# Rus.net
KiCad netlist of a schematic drawn in Altium Designer
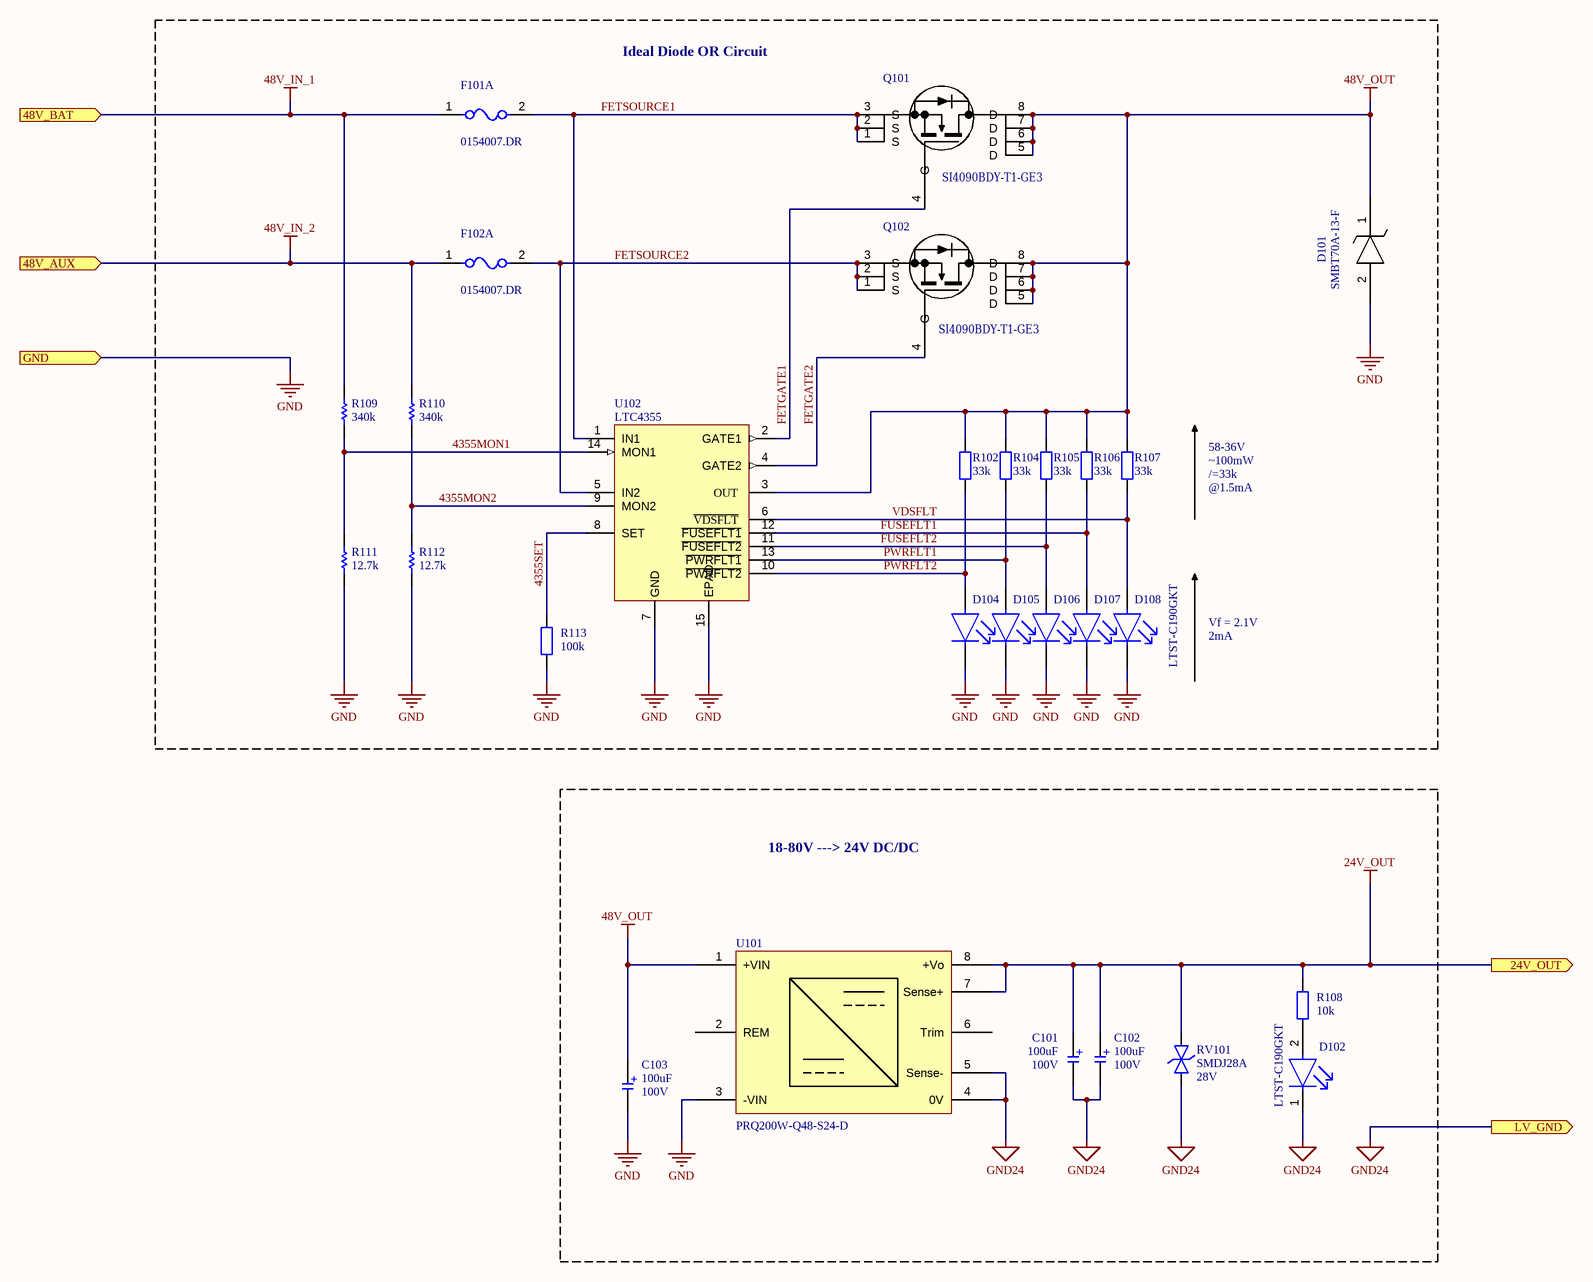
[diagram p0: Rus.SchDoc]

(export (version "E")
  (design (tool "Eeschema 10.0.6"))
  (components
    (comp (ref "C101")
      (value "EMVE101ARA101MKE0S")
      (footprint "CAP ALSMD ELEC 12.5MM H13MM")
      (description "Generic Polarised Capacitor")
      (fields
        (field (name "TOLERANCE") "20%")
        (field (name "VOLTAGE RATING") "100V")
        (field (name "CAPACITANCE") "100uF")
        (field (name "MANUFACTURER") "United Chemi-Con")
      )
      (libsource (lib "DMR_common_lib") (part "C_POL"))
    )
    (comp (ref "C102")
      (value "EMVE101ARA101MKE0S")
      (footprint "CAP ALSMD ELEC 12.5MM H13MM")
      (description "Generic Polarised Capacitor")
      (fields
        (field (name "TOLERANCE") "20%")
        (field (name "VOLTAGE RATING") "100V")
        (field (name "CAPACITANCE") "100uF")
        (field (name "MANUFACTURER") "United Chemi-Con")
      )
      (libsource (lib "DMR_common_lib") (part "C_POL"))
    )
    (comp (ref "C103")
      (value "EMVE101ARA101MKE0S")
      (footprint "CAP ALSMD ELEC 12.5MM H13MM")
      (description "Generic Polarised Capacitor")
      (fields
        (field (name "TOLERANCE") "20%")
        (field (name "VOLTAGE RATING") "100V")
        (field (name "CAPACITANCE") "100uF")
        (field (name "MANUFACTURER") "United Chemi-Con")
      )
      (libsource (lib "DMR_common_lib") (part "C_POL"))
    )
    (comp (ref "D101")
      (value "SMBT70A-13-F")
      (footprint "SMBT70A-13-F")
      (description "SMBJ Series 70 V 600 W Surface Mount Uni-Directional TVS Diode - DO-214AA")
      (fields (field (name "MANUFACTURER") "Diodes"))
      (libsource (lib "Schlib1") (part "SMBT70A-13-F"))
    )
    (comp (ref "D102")
      (value "LTST-C190GKT")
      (footprint "FP-LTST-C190GKT-MFG")
      (description "LED GREEN CLEAR CHIP SMD")
      (fields (field (name "VOLTAGE") "2V"))
      (libsource (lib "") (part "8706943c75ba83719d021d2fdc84c58_1"))
    )
    (comp (ref "D104")
      (value "LTST-C190GKT")
      (footprint "FP-LTST-C190GKT-MFG")
      (description "LED GREEN CLEAR CHIP SMD")
      (fields (field (name "VOLTAGE") "2V"))
      (libsource (lib "Altium Content Vault") (part "8706943c75ba83719d021d2fdc84c58"))
    )
    (comp (ref "D105")
      (value "LTST-C190GKT")
      (footprint "FP-LTST-C190GKT-MFG")
      (description "LED GREEN CLEAR CHIP SMD")
      (fields (field (name "VOLTAGE") "2V"))
      (libsource (lib "Altium Content Vault") (part "8706943c75ba83719d021d2fdc84c58"))
    )
    (comp (ref "D106")
      (value "LTST-C190GKT")
      (footprint "FP-LTST-C190GKT-MFG")
      (description "LED GREEN CLEAR CHIP SMD")
      (fields (field (name "VOLTAGE") "2V"))
      (libsource (lib "Altium Content Vault") (part "8706943c75ba83719d021d2fdc84c58"))
    )
    (comp (ref "D107")
      (value "LTST-C190GKT")
      (footprint "FP-LTST-C190GKT-MFG")
      (description "LED GREEN CLEAR CHIP SMD")
      (fields (field (name "VOLTAGE") "2V"))
      (libsource (lib "Altium Content Vault") (part "8706943c75ba83719d021d2fdc84c58"))
    )
    (comp (ref "D108")
      (value "LTST-C190GKT")
      (footprint "FP-LTST-C190GKT-MFG")
      (description "LED GREEN CLEAR CHIP SMD")
      (fields (field (name "VOLTAGE") "2V"))
      (libsource (lib "Altium Content Vault") (part "8706943c75ba83719d021d2fdc84c58"))
    )
    (comp (ref "F101A")
      (value "0154007.DR")
      (footprint "FP-0154-MFG")
      (description "FUSE BRD MNT 7A 125VAC/VDC 2SMD")
      (fields
        (field (name "OCTOPART") "https://octopart.com/0154007.dr-littelfuse-565863")
        (field (name "MANUFACTURER") "Littelfuse Inc")
      )
      (libsource (lib "Altium Content Vault") (part "5bcf9b9f640e542cf0359d10258e979"))
    )
    (comp (ref "F102A")
      (value "0154007.DR")
      (footprint "FP-0154-MFG")
      (description "FUSE BRD MNT 7A 125VAC/VDC 2SMD")
      (fields
        (field (name "OCTOPART") "https://octopart.com/0154007.dr-littelfuse-565863")
        (field (name "MANUFACTURER") "Littelfuse Inc")
      )
      (libsource (lib "Altium Content Vault") (part "5bcf9b9f640e542cf0359d10258e979"))
    )
    (comp (ref "Q101")
      (value "‎SI4090BDY-T1-GE3‎")
      (footprint "SOIC127P600X175-8N")
      (fields (field (name "MANUFACTURER PART NUMBER") "SI4090BDY-T1-GE3"))
      (libsource (lib "Schlib1") (part "‎SI4090BDY-T1-GE3‎"))
    )
    (comp (ref "Q102")
      (value "‎SI4090BDY-T1-GE3‎")
      (footprint "SOIC127P600X175-8N")
      (fields (field (name "MANUFACTURER PART NUMBER") "SI4090BDY-T1-GE3"))
      (libsource (lib "Schlib1") (part "‎SI4090BDY-T1-GE3‎"))
    )
    (comp (ref "R102")
      (value "33k")
      (footprint "RES 0603_1608 RF")
      (description "Generic Resistor")
      (fields (field (name "TOLERANCE") "1%"))
      (libsource (lib "DMR_common_lib") (part "R"))
    )
    (comp (ref "R104")
      (value "33k")
      (footprint "RES 0603_1608 RF")
      (description "Generic Resistor")
      (fields (field (name "TOLERANCE") "1%"))
      (libsource (lib "DMR_common_lib") (part "R"))
    )
    (comp (ref "R105")
      (value "33k")
      (footprint "RES 0603_1608 RF")
      (description "Generic Resistor")
      (fields (field (name "TOLERANCE") "1%"))
      (libsource (lib "DMR_common_lib") (part "R"))
    )
    (comp (ref "R106")
      (value "33k")
      (footprint "RES 0603_1608 RF")
      (description "Generic Resistor")
      (fields (field (name "TOLERANCE") "1%"))
      (libsource (lib "DMR_common_lib") (part "R"))
    )
    (comp (ref "R107")
      (value "33k")
      (footprint "RES 0603_1608 RF")
      (description "Generic Resistor")
      (fields (field (name "TOLERANCE") "1%"))
      (libsource (lib "DMR_common_lib") (part "R"))
    )
    (comp (ref "R108")
      (value "10k")
      (footprint "RES 0402_1005 RF")
      (description "Generic Resistor")
      (fields (field (name "TOLERANCE") "1%"))
      (libsource (lib "DMR_common_lib") (part "R"))
    )
    (comp (ref "R109")
      (value "ERA6AEB3403V")
      (footprint "RESC2013X60X40NL20T25")
      (fields (field (name "MANUFACTURER") "Panasonic") (field (name "RESISTANCE") "340k"))
      (libsource (lib "Altium Content Vault") (part "RES"))
    )
    (comp (ref "R110")
      (value "ERA6AEB3403V")
      (footprint "RESC2013X60X40NL20T25")
      (fields (field (name "MANUFACTURER") "Panasonic") (field (name "RESISTANCE") "340k"))
      (libsource (lib "Altium Content Vault") (part "RES"))
    )
    (comp (ref "R111")
      (value "ERJ-3EKF1272V")
      (footprint "RESC1608X55X30LL15T15")
      (fields (field (name "MANUFACTURER") "Panasonic") (field (name "RESISTANCE") "12.7k"))
      (libsource (lib "Altium Content Vault") (part "RES"))
    )
    (comp (ref "R112")
      (value "ERJ-3EKF1272V")
      (footprint "RESC1608X55X30LL15T15")
      (fields (field (name "MANUFACTURER") "Panasonic") (field (name "RESISTANCE") "12.7k"))
      (libsource (lib "Altium Content Vault") (part "RES"))
    )
    (comp (ref "R113")
      (value "100k")
      (footprint "RES 0402_1005 RF")
      (description "Generic Resistor")
      (fields (field (name "TOLERANCE") "1%"))
      (libsource (lib "DMR_common_lib") (part "R"))
    )
    (comp (ref "RV101")
      (value "SMDJ28A")
      (footprint "DO214AB SMC")
      (description "J Series 31.1 V 3000 W Surface Mount Uni-Directional TVS Diode - DO-214AB")
      (fields (field (name "MANUFACTURER") "Littelfuse") (field (name "OPERATING SUPPLY VOLTAGE") "28V"))
      (libsource (lib "DMR_common_lib") (part "SMDJ28A"))
    )
    (comp (ref "U101")
      (value "PRQ200W-Q48-S24-D")
      (footprint "DIP BRICK QUARTER")
      (description "24 Vdc, 8.4 A, 201.6 W, 18~75 Vdc Input Range")
      (fields (field (name "MANUFACTURER") "CUI Inc"))
      (libsource (lib "DMR_common_lib") (part "PRQ200W-Q48-S24-D"))
    )
    (comp (ref "U102")
      (value "LTC4355IDE#PBF")
      (footprint "DFN-14_DE_LIT")
      (fields (field (name "MANUFACTURER") "Analog Devices") (field (name "COLLOQUIAL") "LTC4355"))
      (libsource (lib "DMR_common_lib") (part "LTC4355IDE#PBF"))
    )
  )
  (nets
    (net (code "1") (name "/4355MON1") (class "Default")
      (node (ref "R109") (pin "1") (pinfunction "1_1") (pintype "passive"))
      (node (ref "R111") (pin "2") (pinfunction "2_2") (pintype "passive"))
      (node (ref "U102") (pin "14") (pinfunction "MON1_14") (pintype "input"))
    )
    (net (code "2") (name "/4355MON2") (class "Default")
      (node (ref "R110") (pin "1") (pinfunction "1_1") (pintype "passive"))
      (node (ref "R112") (pin "2") (pinfunction "2_2") (pintype "passive"))
      (node (ref "U102") (pin "9") (pinfunction "MON2_9") (pintype "passive"))
    )
    (net (code "3") (name "/4355SET") (class "Default")
      (node (ref "R113") (pin "2") (pinfunction "2_2") (pintype "passive"))
      (node (ref "U102") (pin "8") (pinfunction "SET_8") (pintype "passive"))
    )
    (net (code "4") (name "/FETGATE1") (class "Default")
      (node (ref "Q101") (pin "4") (pinfunction "G_4") (pintype "passive"))
      (node (ref "U102") (pin "2") (pinfunction "GATE1_2") (pintype "output"))
    )
    (net (code "5") (name "/FETGATE2") (class "Default")
      (node (ref "Q102") (pin "4") (pinfunction "G_4") (pintype "passive"))
      (node (ref "U102") (pin "4") (pinfunction "GATE2_4") (pintype "output"))
    )
    (net (code "6") (name "/FETSOURCE1") (class "Default")
      (node (ref "F101A") (pin "2") (pinfunction "2_2") (pintype "passive"))
      (node (ref "Q101") (pin "1") (pinfunction "S_1") (pintype "passive"))
      (node (ref "Q101") (pin "2") (pinfunction "S_2") (pintype "passive"))
      (node (ref "Q101") (pin "3") (pinfunction "S_3") (pintype "passive"))
      (node (ref "U102") (pin "1") (pinfunction "IN1_1") (pintype "passive"))
    )
    (net (code "7") (name "/FETSOURCE2") (class "Default")
      (node (ref "F102A") (pin "2") (pinfunction "2_2") (pintype "passive"))
      (node (ref "Q102") (pin "1") (pinfunction "S_1") (pintype "passive"))
      (node (ref "Q102") (pin "2") (pinfunction "S_2") (pintype "passive"))
      (node (ref "Q102") (pin "3") (pinfunction "S_3") (pintype "passive"))
      (node (ref "U102") (pin "5") (pinfunction "IN2_5") (pintype "passive"))
    )
    (net (code "8") (name "/FUSEFLT1") (class "Default")
      (node (ref "D107") (pin "2") (pinfunction "A_2") (pintype "passive"))
      (node (ref "R106") (pin "1") (pinfunction "1_1") (pintype "passive"))
      (node (ref "U102") (pin "12") (pinfunction "~{FUSEFLT1}_12") (pintype "passive"))
    )
    (net (code "9") (name "/FUSEFLT2") (class "Default")
      (node (ref "D106") (pin "2") (pinfunction "A_2") (pintype "passive"))
      (node (ref "R105") (pin "1") (pinfunction "1_1") (pintype "passive"))
      (node (ref "U102") (pin "11") (pinfunction "~{FUSEFLT2}_11") (pintype "passive"))
    )
    (net (code "10") (name "/PWRFLT1") (class "Default")
      (node (ref "D105") (pin "2") (pinfunction "A_2") (pintype "passive"))
      (node (ref "R104") (pin "1") (pinfunction "1_1") (pintype "passive"))
      (node (ref "U102") (pin "13") (pinfunction "~{PWRFLT1}_13") (pintype "passive"))
    )
    (net (code "11") (name "/PWRFLT2") (class "Default")
      (node (ref "D104") (pin "2") (pinfunction "A_2") (pintype "passive"))
      (node (ref "R102") (pin "1") (pinfunction "1_1") (pintype "passive"))
      (node (ref "U102") (pin "10") (pinfunction "~{PWRFLT2}_10") (pintype "passive"))
    )
    (net (code "12") (name "/VDSFLT") (class "Default")
      (node (ref "D108") (pin "2") (pinfunction "A_2") (pintype "passive"))
      (node (ref "R107") (pin "1") (pinfunction "1_1") (pintype "passive"))
      (node (ref "U102") (pin "6") (pinfunction "~{VDSFLT}_6") (pintype "passive"))
    )
    (net (code "13") (name "24V_OUT") (class "Default")
      (node (ref "C101") (pin "1") (pinfunction "1_1") (pintype "passive"))
      (node (ref "C102") (pin "1") (pinfunction "1_1") (pintype "passive"))
      (node (ref "R108") (pin "2") (pinfunction "2_2") (pintype "passive"))
      (node (ref "RV101") (pin "2") (pinfunction "2_2") (pintype "passive"))
      (node (ref "U101") (pin "7") (pinfunction "Sense+_7") (pintype "passive"))
      (node (ref "U101") (pin "8") (pinfunction "+Vo_8") (pintype "power_in"))
    )
    (net (code "14") (name "48V_IN_1") (class "Default")
      (node (ref "F101A") (pin "1") (pinfunction "1_1") (pintype "passive"))
      (node (ref "R109") (pin "2") (pinfunction "2_2") (pintype "passive"))
    )
    (net (code "15") (name "48V_IN_2") (class "Default")
      (node (ref "F102A") (pin "1") (pinfunction "1_1") (pintype "passive"))
      (node (ref "R110") (pin "2") (pinfunction "2_2") (pintype "passive"))
    )
    (net (code "16") (name "48V_OUT") (class "Default")
      (node (ref "C103") (pin "1") (pinfunction "1_1") (pintype "passive"))
      (node (ref "D101") (pin "1") (pintype "passive"))
      (node (ref "Q101") (pin "5") (pinfunction "D_5") (pintype "passive"))
      (node (ref "Q101") (pin "6") (pinfunction "D_6") (pintype "passive"))
      (node (ref "Q101") (pin "7") (pinfunction "D_7") (pintype "passive"))
      (node (ref "Q101") (pin "8") (pinfunction "D_8") (pintype "passive"))
      (node (ref "Q102") (pin "5") (pinfunction "D_5") (pintype "passive"))
      (node (ref "Q102") (pin "6") (pinfunction "D_6") (pintype "passive"))
      (node (ref "Q102") (pin "7") (pinfunction "D_7") (pintype "passive"))
      (node (ref "Q102") (pin "8") (pinfunction "D_8") (pintype "passive"))
      (node (ref "R102") (pin "2") (pinfunction "2_2") (pintype "passive"))
      (node (ref "R104") (pin "2") (pinfunction "2_2") (pintype "passive"))
      (node (ref "R105") (pin "2") (pinfunction "2_2") (pintype "passive"))
      (node (ref "R106") (pin "2") (pinfunction "2_2") (pintype "passive"))
      (node (ref "R107") (pin "2") (pinfunction "2_2") (pintype "passive"))
      (node (ref "U101") (pin "1") (pinfunction "+VIN_1") (pintype "power_in"))
      (node (ref "U102") (pin "3") (pinfunction "OUT_3") (pintype "passive"))
    )
    (net (code "17") (name "GND") (class "Default")
      (node (ref "C103") (pin "2") (pinfunction "2_2") (pintype "passive"))
      (node (ref "D101") (pin "2") (pintype "passive"))
      (node (ref "D104") (pin "1") (pinfunction "C_1") (pintype "passive"))
      (node (ref "D105") (pin "1") (pinfunction "C_1") (pintype "passive"))
      (node (ref "D106") (pin "1") (pinfunction "C_1") (pintype "passive"))
      (node (ref "D107") (pin "1") (pinfunction "C_1") (pintype "passive"))
      (node (ref "D108") (pin "1") (pinfunction "C_1") (pintype "passive"))
      (node (ref "R111") (pin "1") (pinfunction "1_1") (pintype "passive"))
      (node (ref "R112") (pin "1") (pinfunction "1_1") (pintype "passive"))
      (node (ref "R113") (pin "1") (pinfunction "1_1") (pintype "passive"))
      (node (ref "U101") (pin "3") (pinfunction "-VIN_3") (pintype "power_in"))
      (node (ref "U102") (pin "15") (pinfunction "EPAD_15") (pintype "power_in"))
      (node (ref "U102") (pin "7") (pinfunction "GND_7") (pintype "power_in"))
    )
    (net (code "18") (name "GND24") (class "Default")
      (node (ref "C101") (pin "2") (pinfunction "2_2") (pintype "passive"))
      (node (ref "C102") (pin "2") (pinfunction "2_2") (pintype "passive"))
      (node (ref "D102") (pin "1") (pinfunction "C_1") (pintype "passive"))
      (node (ref "RV101") (pin "1") (pinfunction "1_1") (pintype "passive"))
      (node (ref "U101") (pin "4") (pinfunction "0V_4") (pintype "power_in"))
      (node (ref "U101") (pin "5") (pinfunction "Sense-_5") (pintype "passive"))
    )
    (net (code "19") (name "Net-(D102-A)") (class "Default")
      (node (ref "D102") (pin "2") (pinfunction "A_2") (pintype "passive"))
      (node (ref "R108") (pin "1") (pinfunction "1_1") (pintype "passive"))
    )
    (net (code "20") (name "unconnected-(U101-REM-Pad2)") (class "Default")
      (node (ref "U101") (pin "2") (pinfunction "REM_2") (pintype "passive"))
    )
    (net (code "21") (name "unconnected-(U101-Trim-Pad6)") (class "Default")
      (node (ref "U101") (pin "6") (pinfunction "Trim_6") (pintype "passive"))
    )
  )
)
